# BluePillShematic.net
KiCad netlist of a schematic drawn in Altium Designer
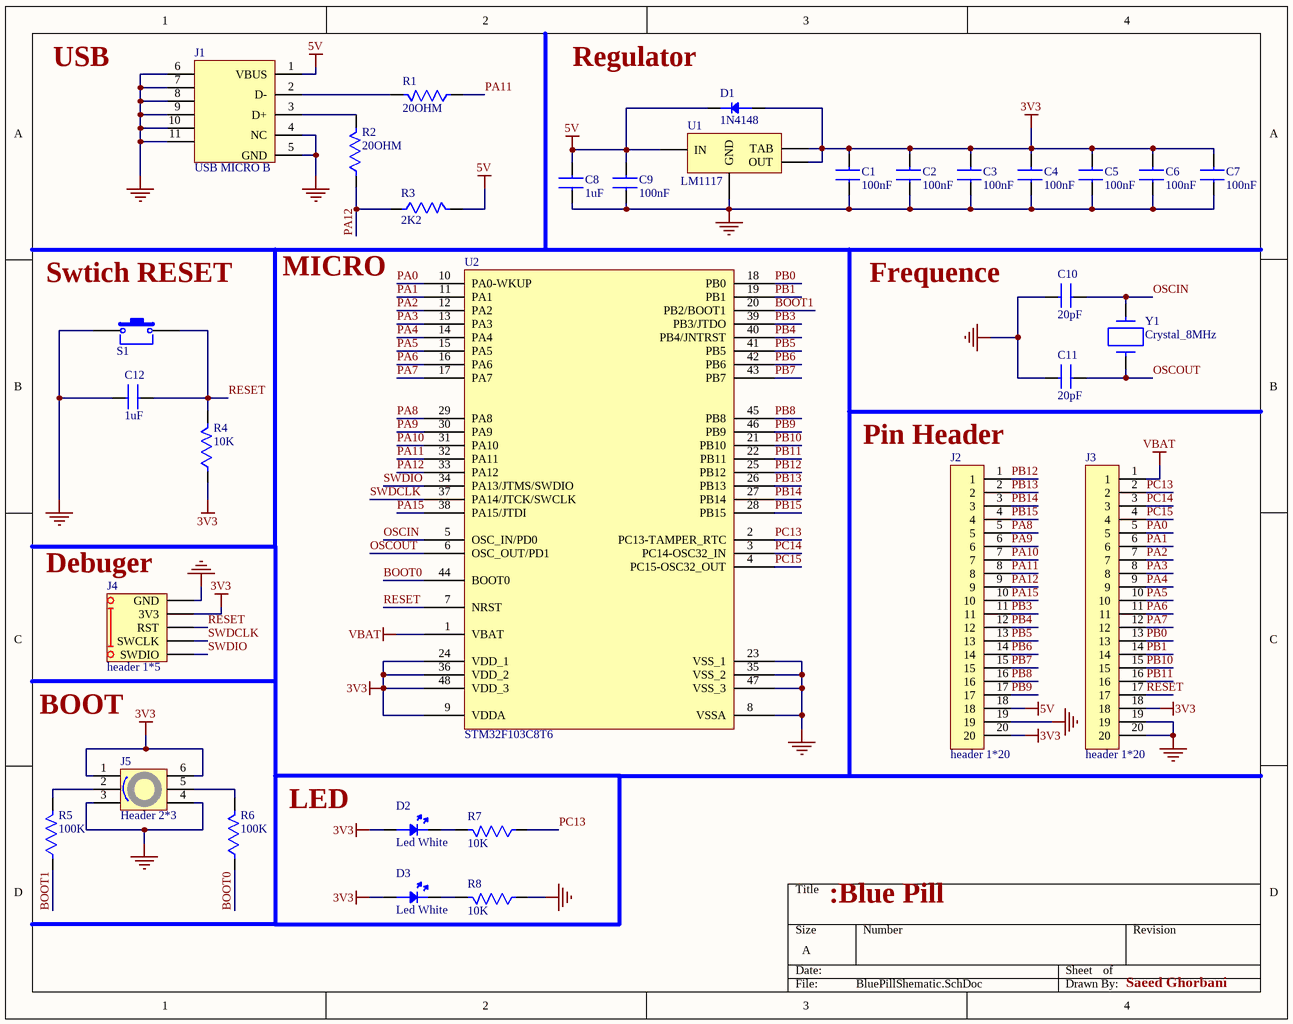
[diagram p0: BluePillShematic.SchDoc]

(export (version "E")
  (design (tool "Eeschema 10.0.6"))
  (components
    (comp (ref "C1")
      (value "100nF")
      (footprint "C0805")
      (description "Cap Ceramic 0.1uF 50V X7R 10% Pad SMD 0805 (1%FR) 125C")
      (fields
        (field (name "MANUFACTURER") "KEMET")
        (field (name "MANUFACTURER PART NUMBER") "M3253504E2A104KZMB")
      )
      (libsource (lib "BluePillShematicLibrary") (part "C0805_100nF"))
    )
    (comp (ref "C2")
      (value "100nF")
      (footprint "C0805")
      (description "Cap Ceramic 0.1uF 50V X7R 10% Pad SMD 0805 (1%FR) 125C")
      (fields
        (field (name "MANUFACTURER") "KEMET")
        (field (name "MANUFACTURER PART NUMBER") "M3253504E2A104KZMB")
      )
      (libsource (lib "BluePillShematicLibrary") (part "C0805_100nF"))
    )
    (comp (ref "C3")
      (value "100nF")
      (footprint "C0805")
      (description "Cap Ceramic 0.1uF 50V X7R 10% Pad SMD 0805 (1%FR) 125C")
      (fields
        (field (name "MANUFACTURER") "KEMET")
        (field (name "MANUFACTURER PART NUMBER") "M3253504E2A104KZMB")
      )
      (libsource (lib "BluePillShematicLibrary") (part "C0805_100nF"))
    )
    (comp (ref "C4")
      (value "100nF")
      (footprint "C0805")
      (description "Cap Ceramic 0.1uF 50V X7R 10% Pad SMD 0805 (1%FR) 125C")
      (fields
        (field (name "MANUFACTURER") "KEMET")
        (field (name "MANUFACTURER PART NUMBER") "M3253504E2A104KZMB")
      )
      (libsource (lib "BluePillShematicLibrary") (part "C0805_100nF"))
    )
    (comp (ref "C5")
      (value "100nF")
      (footprint "C0805")
      (description "Cap Ceramic 0.1uF 50V X7R 10% Pad SMD 0805 (1%FR) 125C")
      (fields
        (field (name "MANUFACTURER") "KEMET")
        (field (name "MANUFACTURER PART NUMBER") "M3253504E2A104KZMB")
      )
      (libsource (lib "BluePillShematicLibrary") (part "C0805_100nF"))
    )
    (comp (ref "C6")
      (value "100nF")
      (footprint "C0805")
      (description "Cap Ceramic 0.1uF 50V X7R 10% Pad SMD 0805 (1%FR) 125C")
      (fields
        (field (name "MANUFACTURER") "KEMET")
        (field (name "MANUFACTURER PART NUMBER") "M3253504E2A104KZMB")
      )
      (libsource (lib "BluePillShematicLibrary") (part "C0805_100nF"))
    )
    (comp (ref "C7")
      (value "100nF")
      (footprint "C0805")
      (description "Cap Ceramic 0.1uF 50V X7R 10% Pad SMD 0805 (1%FR) 125C")
      (fields
        (field (name "MANUFACTURER") "KEMET")
        (field (name "MANUFACTURER PART NUMBER") "M3253504E2A104KZMB")
      )
      (libsource (lib "BluePillShematicLibrary") (part "C0805_100nF"))
    )
    (comp (ref "C8")
      (value "1uF")
      (footprint "C0805")
      (fields
        (field (name "MANUFACTURER") "KEMET")
        (field (name "MANUFACTURER PART NUMBER") "C0805C105K5PACTU")
        (field (name "TOLERANCE") "10%")
      )
      (libsource (lib "BluePillShematicLibrary") (part "C0805_1uF"))
    )
    (comp (ref "C9")
      (value "100nF")
      (footprint "C0805")
      (description "Cap Ceramic 0.1uF 50V X7R 10% Pad SMD 0805 (1%FR) 125C")
      (fields
        (field (name "MANUFACTURER") "KEMET")
        (field (name "MANUFACTURER PART NUMBER") "M3253504E2A104KZMB")
      )
      (libsource (lib "BluePillShematicLibrary") (part "C0805_100nF"))
    )
    (comp (ref "C10")
      (value "20pF")
      (footprint "C0805")
      (description "Cap Ceramic 20pF 50V C0G 10% SMD 0805 125°C Paper T/R")
      (fields
        (field (name "MANUFACTURER") "KEMET")
        (field (name "MANUFACTURER PART NUMBER") "C0805C200K5GAC7800")
      )
      (libsource (lib "BluePillShematicLibrary") (part "C0805_20pF"))
    )
    (comp (ref "C11")
      (value "20pF")
      (footprint "C0805")
      (description "Cap Ceramic 20pF 50V C0G 10% SMD 0805 125°C Paper T/R")
      (fields
        (field (name "MANUFACTURER") "KEMET")
        (field (name "MANUFACTURER PART NUMBER") "C0805C200K5GAC7800")
      )
      (libsource (lib "BluePillShematicLibrary") (part "C0805_20pF"))
    )
    (comp (ref "C12")
      (value "1uF")
      (footprint "C0805")
      (fields
        (field (name "MANUFACTURER") "KEMET")
        (field (name "MANUFACTURER PART NUMBER") "C0805C105K5PACTU")
        (field (name "TOLERANCE") "10%")
      )
      (libsource (lib "BluePillShematicLibrary") (part "C0805_1uF"))
    )
    (comp (ref "D1")
      (value "1N4148")
      (footprint "DO-213-A")
      (description "Diode Switching 75V 0.2A 2-Pin DO-213AA")
      (fields
        (field (name "MANUFACTURER") "Microsemi")
        (field (name "MANUFACTURER PART NUMBER") "1N4148UR-1")
      )
      (libsource (lib "BluePillShematicLibrary") (part "1N4148UR-1"))
    )
    (comp (ref "D2")
      (value "Led White")
      (footprint "LED0603")
      (description "Led White Clear 0603 SMD")
      (fields (field (name "MANUFACTURER") "Inolux") (field (name "MANUFACTURER PART NUMBER") "IN-S63AT5UW"))
      (libsource (lib "BluePillShematicLibrary") (part "LED0603"))
    )
    (comp (ref "D3")
      (value "Led White")
      (footprint "LED0603")
      (description "Led White Clear 0603 SMD")
      (fields (field (name "MANUFACTURER") "Inolux") (field (name "MANUFACTURER PART NUMBER") "IN-S63AT5UW"))
      (libsource (lib "BluePillShematicLibrary") (part "LED0603"))
    )
    (comp (ref "J1")
      (value "USB MICRO B")
      (footprint "USB")
      (description "CONN USB MICRO B RECPT SMT R/A")
      (fields
        (field (name "MANUFACTURER") "Amphenol ICC / FCI")
        (field (name "MANUFACTURER PART NUMBER") "10118194-0001LF")
      )
      (libsource (lib "BluePillShematicLibrary") (part "USB MICRO B"))
    )
    (comp (ref "J2")
      (value "header 1*20")
      (footprint "header 1*20")
      (fields (field (name "MANUFACTURER") "Harwin") (field (name "MANUFACTURER PART NUMBER") "M20-9992045"))
      (libsource (lib "BluePillShematicLibrary") (part "header 1*20"))
    )
    (comp (ref "J3")
      (value "header 1*20")
      (footprint "header 1*20")
      (fields (field (name "MANUFACTURER") "Harwin") (field (name "MANUFACTURER PART NUMBER") "M20-9992045"))
      (libsource (lib "BluePillShematicLibrary") (part "header 1*20"))
    )
    (comp (ref "J4")
      (value "header 1*5")
      (footprint "header 1*5")
      (description "M20 Header,  Pin,  Sil,  Vertical,  5 W")
      (fields (field (name "MANUFACTURER") "Harwin") (field (name "MANUFACTURER PART NUMBER") "M20-9990545"))
      (libsource (lib "BluePillShematicLibrary") (part "header 1*5"))
    )
    (comp (ref "J5")
      (value "Header 2*3")
      (footprint "header 2*3")
      (fields (field (name "MANUFACTURER") "Harwin") (field (name "MANUFACTURER PART NUMBER") "M20-9980345"))
      (libsource (lib "BluePillShematicLibrary") (part "Header 2*3"))
    )
    (comp (ref "R1")
      (value "20OHM")
      (footprint "R0805")
      (description "RES SMD 20 OHM 0.1% 1/8W 0805")
      (fields
        (field (name "MANUFACTURER") "Yageo")
        (field (name "MANUFACTURER PART NUMBER") "RT0805BRD0720RL")
      )
      (libsource (lib "BluePillShematicLibrary") (part "R0805_20OHM"))
    )
    (comp (ref "R2")
      (value "20OHM")
      (footprint "R0805")
      (description "RES SMD 20 OHM 0.1% 1/8W 0805")
      (fields
        (field (name "MANUFACTURER") "Yageo")
        (field (name "MANUFACTURER PART NUMBER") "RT0805BRD0720RL")
      )
      (libsource (lib "BluePillShematicLibrary") (part "R0805_20OHM"))
    )
    (comp (ref "R3")
      (value "2K2")
      (footprint "R0805")
      (description "Res Thick Film 0805 2.2K Ohm 5% 0.125W(1/8W) ±100ppm/C Epoxy Pad SMD T/R")
      (fields
        (field (name "MANUFACTURER") "Yageo")
        (field (name "MANUFACTURER PART NUMBER") "RC0805JR-072K2L")
      )
      (libsource (lib "BluePillShematicLibrary") (part "R0805_2K2"))
    )
    (comp (ref "R4")
      (value "10K")
      (footprint "R0805")
      (description "Res Thick Film 0805 10K Ohm 1% 0.5W(1/2W) ±200ppm/C Pad SMD Automotive T/R")
      (fields
        (field (name "MANUFACTURER") "Yageo")
        (field (name "MANUFACTURER PART NUMBER") "SR0805FR-4710KL")
      )
      (libsource (lib "BluePillShematicLibrary") (part "R0805_10K"))
    )
    (comp (ref "R5")
      (value "100K")
      (footprint "R0805")
      (fields
        (field (name "MANUFACTURER") "Yageo")
        (field (name "MANUFACTURER PART NUMBER") "AC0805FR-7W100KL")
      )
      (libsource (lib "BluePillShematicLibrary") (part "R0805_100K"))
    )
    (comp (ref "R6")
      (value "100K")
      (footprint "R0805")
      (fields
        (field (name "MANUFACTURER") "Yageo")
        (field (name "MANUFACTURER PART NUMBER") "AC0805FR-7W100KL")
      )
      (libsource (lib "BluePillShematicLibrary") (part "R0805_100K"))
    )
    (comp (ref "R7")
      (value "10K")
      (footprint "R0805")
      (description "Res Thick Film 0805 10K Ohm 1% 0.5W(1/2W) ±200ppm/C Pad SMD Automotive T/R")
      (fields
        (field (name "MANUFACTURER") "Yageo")
        (field (name "MANUFACTURER PART NUMBER") "SR0805FR-4710KL")
      )
      (libsource (lib "BluePillShematicLibrary") (part "R0805_10K"))
    )
    (comp (ref "R8")
      (value "10K")
      (footprint "R0805")
      (description "Res Thick Film 0805 10K Ohm 1% 0.5W(1/2W) ±200ppm/C Pad SMD Automotive T/R")
      (fields
        (field (name "MANUFACTURER") "Yageo")
        (field (name "MANUFACTURER PART NUMBER") "SR0805FR-4710KL")
      )
      (libsource (lib "BluePillShematicLibrary") (part "R0805_10K"))
    )
    (comp (ref "S1")
      (value "PTS636SMG25JSMTRLFS")
      (footprint "Switch Reset")
      (fields (field (name "MANUFACTURER") "ITT C&K"))
      (libsource (lib "BluePillShematicLibrary") (part "Switch Reset"))
    )
    (comp (ref "U1")
      (value "LM1117")
      (footprint "LM1117_SOP")
      (fields
        (field (name "MANUFACTURER") "TI National Semiconductor")
        (field (name "MANUFACTURER PART NUMBER") "LM1117MP-3.3/NOPB")
      )
      (libsource (lib "BluePillShematicLibrary") (part "LM1117"))
    )
    (comp (ref "U2")
      (value "STM32F103C8T6")
      (footprint "TQFP48")
      (fields (field (name "MANUFACTURER") "STMicroelectronics"))
      (libsource (lib "BluePillShematicLibrary") (part "STM32F103C8T6"))
    )
    (comp (ref "Y1")
      (value "Crystal_8MHz")
      (footprint "Crystal_8MHz")
      (description "Crystal 8MHz ±30ppm (Tol) ±50ppm (Stability) 18pF FUND 60Ohm 2-Pin HC-49/USX SMD T/R")
      (fields
        (field (name "MANUFACTURER") "ECS International")
        (field (name "MANUFACTURER PART NUMBER") "ECS-80-18-5PX-TR")
      )
      (libsource (lib "BluePillShematicLibrary") (part "Crystal_8MHz"))
    )
  )
  (nets
    (net (code "1") (name "/BOOT0") (class "Default")
      (node (ref "R6") (pin "1") (pinfunction "1_1") (pintype "passive"))
      (node (ref "U2") (pin "44") (pinfunction "BOOT0_44") (pintype "passive"))
    )
    (net (code "2") (name "/BOOT1") (class "Default")
      (node (ref "R5") (pin "1") (pinfunction "1_1") (pintype "passive"))
      (node (ref "U2") (pin "20") (pinfunction "PB2/BOOT1_20") (pintype "passive"))
    )
    (net (code "3") (name "/OSCIN") (class "Default")
      (node (ref "C10") (pin "2") (pinfunction "2_2") (pintype "passive"))
      (node (ref "U2") (pin "5") (pinfunction "OSC_IN/PD0_5") (pintype "passive"))
      (node (ref "Y1") (pin "2") (pinfunction "2_2") (pintype "passive"))
    )
    (net (code "4") (name "/OSCOUT") (class "Default")
      (node (ref "C11") (pin "2") (pinfunction "2_2") (pintype "passive"))
      (node (ref "U2") (pin "6") (pinfunction "OSC_OUT/PD1_6") (pintype "passive"))
      (node (ref "Y1") (pin "1") (pinfunction "1_1") (pintype "passive"))
    )
    (net (code "5") (name "/PA0") (class "Default")
      (node (ref "J3") (pin "5") (pinfunction "5_5") (pintype "passive"))
      (node (ref "U2") (pin "10") (pinfunction "PA0-WKUP_10") (pintype "passive"))
    )
    (net (code "6") (name "/PA1") (class "Default")
      (node (ref "J3") (pin "6") (pinfunction "6_6") (pintype "passive"))
      (node (ref "U2") (pin "11") (pinfunction "PA1_11") (pintype "passive"))
    )
    (net (code "7") (name "/PA2") (class "Default")
      (node (ref "J3") (pin "7") (pinfunction "7_7") (pintype "passive"))
      (node (ref "U2") (pin "12") (pinfunction "PA2_12") (pintype "passive"))
    )
    (net (code "8") (name "/PA3") (class "Default")
      (node (ref "J3") (pin "8") (pinfunction "8_8") (pintype "passive"))
      (node (ref "U2") (pin "13") (pinfunction "PA3_13") (pintype "passive"))
    )
    (net (code "9") (name "/PA4") (class "Default")
      (node (ref "J3") (pin "9") (pinfunction "9_9") (pintype "passive"))
      (node (ref "U2") (pin "14") (pinfunction "PA4_14") (pintype "passive"))
    )
    (net (code "10") (name "/PA5") (class "Default")
      (node (ref "J3") (pin "10") (pinfunction "10_10") (pintype "passive"))
      (node (ref "U2") (pin "15") (pinfunction "PA5_15") (pintype "passive"))
    )
    (net (code "11") (name "/PA6") (class "Default")
      (node (ref "J3") (pin "11") (pinfunction "11_11") (pintype "passive"))
      (node (ref "U2") (pin "16") (pinfunction "PA6_16") (pintype "passive"))
    )
    (net (code "12") (name "/PA7") (class "Default")
      (node (ref "J3") (pin "12") (pinfunction "12_12") (pintype "passive"))
      (node (ref "U2") (pin "17") (pinfunction "PA7_17") (pintype "passive"))
    )
    (net (code "13") (name "/PA8") (class "Default")
      (node (ref "J2") (pin "5") (pinfunction "5_5") (pintype "passive"))
      (node (ref "U2") (pin "29") (pinfunction "PA8_29") (pintype "passive"))
    )
    (net (code "14") (name "/PA9") (class "Default")
      (node (ref "J2") (pin "6") (pinfunction "6_6") (pintype "passive"))
      (node (ref "U2") (pin "30") (pinfunction "PA9_30") (pintype "passive"))
    )
    (net (code "15") (name "/PA10") (class "Default")
      (node (ref "J2") (pin "7") (pinfunction "7_7") (pintype "passive"))
      (node (ref "U2") (pin "31") (pinfunction "PA10_31") (pintype "passive"))
    )
    (net (code "16") (name "/PA11") (class "Default")
      (node (ref "J2") (pin "8") (pinfunction "8_8") (pintype "passive"))
      (node (ref "R1") (pin "1") (pinfunction "1_1") (pintype "passive"))
      (node (ref "U2") (pin "32") (pinfunction "PA11_32") (pintype "passive"))
    )
    (net (code "17") (name "/PA12") (class "Default")
      (node (ref "J2") (pin "9") (pinfunction "9_9") (pintype "passive"))
      (node (ref "R2") (pin "1") (pinfunction "1_1") (pintype "passive"))
      (node (ref "R3") (pin "1") (pinfunction "1_1") (pintype "passive"))
      (node (ref "U2") (pin "33") (pinfunction "PA12_33") (pintype "passive"))
    )
    (net (code "18") (name "/PA15") (class "Default")
      (node (ref "J2") (pin "10") (pinfunction "10_10") (pintype "passive"))
      (node (ref "U2") (pin "38") (pinfunction "PA15/JTDI_38") (pintype "passive"))
    )
    (net (code "19") (name "/PB0") (class "Default")
      (node (ref "J3") (pin "13") (pinfunction "13_13") (pintype "passive"))
      (node (ref "U2") (pin "18") (pinfunction "PB0_18") (pintype "passive"))
    )
    (net (code "20") (name "/PB1") (class "Default")
      (node (ref "J3") (pin "14") (pinfunction "14_14") (pintype "passive"))
      (node (ref "U2") (pin "19") (pinfunction "PB1_19") (pintype "passive"))
    )
    (net (code "21") (name "/PB3") (class "Default")
      (node (ref "J2") (pin "11") (pinfunction "11_11") (pintype "passive"))
      (node (ref "U2") (pin "39") (pinfunction "PB3/JTDO_39") (pintype "passive"))
    )
    (net (code "22") (name "/PB4") (class "Default")
      (node (ref "J2") (pin "12") (pinfunction "12_12") (pintype "passive"))
      (node (ref "U2") (pin "40") (pinfunction "PB4/JNTRST_40") (pintype "passive"))
    )
    (net (code "23") (name "/PB5") (class "Default")
      (node (ref "J2") (pin "13") (pinfunction "13_13") (pintype "passive"))
      (node (ref "U2") (pin "41") (pinfunction "PB5_41") (pintype "passive"))
    )
    (net (code "24") (name "/PB6") (class "Default")
      (node (ref "J2") (pin "14") (pinfunction "14_14") (pintype "passive"))
      (node (ref "U2") (pin "42") (pinfunction "PB6_42") (pintype "passive"))
    )
    (net (code "25") (name "/PB7") (class "Default")
      (node (ref "J2") (pin "15") (pinfunction "15_15") (pintype "passive"))
      (node (ref "U2") (pin "43") (pinfunction "PB7_43") (pintype "passive"))
    )
    (net (code "26") (name "/PB8") (class "Default")
      (node (ref "J2") (pin "16") (pinfunction "16_16") (pintype "passive"))
      (node (ref "U2") (pin "45") (pinfunction "PB8_45") (pintype "passive"))
    )
    (net (code "27") (name "/PB9") (class "Default")
      (node (ref "J2") (pin "17") (pinfunction "17_17") (pintype "passive"))
      (node (ref "U2") (pin "46") (pinfunction "PB9_46") (pintype "passive"))
    )
    (net (code "28") (name "/PB10") (class "Default")
      (node (ref "J3") (pin "15") (pinfunction "15_15") (pintype "passive"))
      (node (ref "U2") (pin "21") (pinfunction "PB10_21") (pintype "passive"))
    )
    (net (code "29") (name "/PB11") (class "Default")
      (node (ref "J3") (pin "16") (pinfunction "16_16") (pintype "passive"))
      (node (ref "U2") (pin "22") (pinfunction "PB11_22") (pintype "passive"))
    )
    (net (code "30") (name "/PB12") (class "Default")
      (node (ref "J2") (pin "1") (pinfunction "1_1") (pintype "passive"))
      (node (ref "U2") (pin "25") (pinfunction "PB12_25") (pintype "passive"))
    )
    (net (code "31") (name "/PB13") (class "Default")
      (node (ref "J2") (pin "2") (pinfunction "2_2") (pintype "passive"))
      (node (ref "U2") (pin "26") (pinfunction "PB13_26") (pintype "passive"))
    )
    (net (code "32") (name "/PB14") (class "Default")
      (node (ref "J2") (pin "3") (pinfunction "3_3") (pintype "passive"))
      (node (ref "U2") (pin "27") (pinfunction "PB14_27") (pintype "passive"))
    )
    (net (code "33") (name "/PB15") (class "Default")
      (node (ref "J2") (pin "4") (pinfunction "4_4") (pintype "passive"))
      (node (ref "U2") (pin "28") (pinfunction "PB15_28") (pintype "passive"))
    )
    (net (code "34") (name "/PC13") (class "Default")
      (node (ref "J3") (pin "2") (pinfunction "2_2") (pintype "passive"))
      (node (ref "R7") (pin "1") (pinfunction "1_1") (pintype "passive"))
      (node (ref "U2") (pin "2") (pinfunction "PC13-TAMPER_RTC_2") (pintype "passive"))
    )
    (net (code "35") (name "/PC14") (class "Default")
      (node (ref "J3") (pin "3") (pinfunction "3_3") (pintype "passive"))
      (node (ref "U2") (pin "3") (pinfunction "PC14-OSC32_IN_3") (pintype "passive"))
    )
    (net (code "36") (name "/PC15") (class "Default")
      (node (ref "J3") (pin "4") (pinfunction "4_4") (pintype "passive"))
      (node (ref "U2") (pin "4") (pinfunction "PC15-OSC32_OUT_4") (pintype "passive"))
    )
    (net (code "37") (name "/RESET") (class "Default")
      (node (ref "C12") (pin "2") (pinfunction "2_2") (pintype "passive"))
      (node (ref "J3") (pin "17") (pinfunction "17_17") (pintype "passive"))
      (node (ref "J4") (pin "3") (pinfunction "RST_3") (pintype "passive"))
      (node (ref "R4") (pin "2") (pinfunction "2_2") (pintype "passive"))
      (node (ref "S1") (pin "2") (pinfunction "2_2") (pintype "passive"))
      (node (ref "U2") (pin "7") (pinfunction "NRST_7") (pintype "passive"))
    )
    (net (code "38") (name "/SWDCLK") (class "Default")
      (node (ref "J4") (pin "4") (pinfunction "SWCLK_4") (pintype "passive"))
      (node (ref "U2") (pin "37") (pinfunction "PA14/JTCK/SWCLK_37") (pintype "passive"))
    )
    (net (code "39") (name "/SWDIO") (class "Default")
      (node (ref "J4") (pin "5") (pinfunction "SWDIO_5") (pintype "passive"))
      (node (ref "U2") (pin "34") (pinfunction "PA13/JTMS/SWDIO_34") (pintype "passive"))
    )
    (net (code "40") (name "3V3") (class "Default")
      (node (ref "C1") (pin "2") (pinfunction "2_2") (pintype "passive"))
      (node (ref "C2") (pin "2") (pinfunction "2_2") (pintype "passive"))
      (node (ref "C3") (pin "2") (pinfunction "2_2") (pintype "passive"))
      (node (ref "C4") (pin "2") (pinfunction "2_2") (pintype "passive"))
      (node (ref "C5") (pin "2") (pinfunction "2_2") (pintype "passive"))
      (node (ref "C6") (pin "2") (pinfunction "2_2") (pintype "passive"))
      (node (ref "C7") (pin "2") (pinfunction "2_2") (pintype "passive"))
      (node (ref "D1") (pin "A") (pinfunction "Anode_A") (pintype "passive"))
      (node (ref "D2") (pin "A") (pinfunction "Anode_A") (pintype "passive"))
      (node (ref "D3") (pin "A") (pinfunction "Anode_A") (pintype "passive"))
      (node (ref "J2") (pin "20") (pinfunction "20_20") (pintype "passive"))
      (node (ref "J3") (pin "18") (pinfunction "18_18") (pintype "passive"))
      (node (ref "J4") (pin "2") (pinfunction "3V3_2") (pintype "passive"))
      (node (ref "J5") (pin "1") (pinfunction "1_1") (pintype "passive"))
      (node (ref "J5") (pin "6") (pinfunction "6_6") (pintype "passive"))
      (node (ref "R4") (pin "1") (pinfunction "1_1") (pintype "passive"))
      (node (ref "U1") (pin "2") (pinfunction "OUT_2") (pintype "passive"))
      (node (ref "U1") (pin "4") (pinfunction "TAB_4") (pintype "passive"))
      (node (ref "U2") (pin "24") (pinfunction "VDD_1_24") (pintype "passive"))
      (node (ref "U2") (pin "36") (pinfunction "VDD_2_36") (pintype "passive"))
      (node (ref "U2") (pin "48") (pinfunction "VDD_3_48") (pintype "passive"))
      (node (ref "U2") (pin "9") (pinfunction "VDDA_9") (pintype "passive"))
    )
    (net (code "41") (name "5V") (class "Default")
      (node (ref "C8") (pin "2") (pinfunction "2_2") (pintype "passive"))
      (node (ref "C9") (pin "2") (pinfunction "2_2") (pintype "passive"))
      (node (ref "D1") (pin "K") (pinfunction "Cathode_K") (pintype "passive"))
      (node (ref "J1") (pin "1") (pinfunction "VBUS_1") (pintype "passive"))
      (node (ref "J2") (pin "18") (pinfunction "18_18") (pintype "passive"))
      (node (ref "R3") (pin "2") (pinfunction "2_2") (pintype "passive"))
      (node (ref "U1") (pin "3") (pinfunction "IN_3") (pintype "passive"))
    )
    (net (code "42") (name "GND") (class "Default")
      (node (ref "C1") (pin "1") (pinfunction "1_1") (pintype "passive"))
      (node (ref "C10") (pin "1") (pinfunction "1_1") (pintype "passive"))
      (node (ref "C11") (pin "1") (pinfunction "1_1") (pintype "passive"))
      (node (ref "C12") (pin "1") (pinfunction "1_1") (pintype "passive"))
      (node (ref "C2") (pin "1") (pinfunction "1_1") (pintype "passive"))
      (node (ref "C3") (pin "1") (pinfunction "1_1") (pintype "passive"))
      (node (ref "C4") (pin "1") (pinfunction "1_1") (pintype "passive"))
      (node (ref "C5") (pin "1") (pinfunction "1_1") (pintype "passive"))
      (node (ref "C6") (pin "1") (pinfunction "1_1") (pintype "passive"))
      (node (ref "C7") (pin "1") (pinfunction "1_1") (pintype "passive"))
      (node (ref "C8") (pin "1") (pinfunction "1_1") (pintype "passive"))
      (node (ref "C9") (pin "1") (pinfunction "1_1") (pintype "passive"))
      (node (ref "J1") (pin "10") (pinfunction "GND_10") (pintype "passive"))
      (node (ref "J1") (pin "11") (pinfunction "GND_11") (pintype "passive"))
      (node (ref "J1") (pin "4") (pinfunction "NC_4") (pintype "passive"))
      (node (ref "J1") (pin "5") (pinfunction "GND_5") (pintype "passive"))
      (node (ref "J1") (pin "6") (pinfunction "GND_6") (pintype "passive"))
      (node (ref "J1") (pin "7") (pinfunction "GND_7") (pintype "passive"))
      (node (ref "J1") (pin "8") (pinfunction "GND_8") (pintype "passive"))
      (node (ref "J1") (pin "9") (pinfunction "GND_9") (pintype "passive"))
      (node (ref "J2") (pin "19") (pinfunction "19_19") (pintype "passive"))
      (node (ref "J3") (pin "19") (pinfunction "19_19") (pintype "passive"))
      (node (ref "J3") (pin "20") (pinfunction "20_20") (pintype "passive"))
      (node (ref "J4") (pin "1") (pinfunction "GND_1") (pintype "passive"))
      (node (ref "J5") (pin "3") (pinfunction "3_3") (pintype "passive"))
      (node (ref "J5") (pin "4") (pinfunction "4_4") (pintype "passive"))
      (node (ref "R8") (pin "1") (pinfunction "1_1") (pintype "passive"))
      (node (ref "S1") (pin "1") (pinfunction "1_1") (pintype "passive"))
      (node (ref "U1") (pin "1") (pinfunction "GND_1") (pintype "passive"))
      (node (ref "U2") (pin "23") (pinfunction "VSS_1_23") (pintype "passive"))
      (node (ref "U2") (pin "35") (pinfunction "VSS_2_35") (pintype "passive"))
      (node (ref "U2") (pin "47") (pinfunction "VSS_3_47") (pintype "passive"))
      (node (ref "U2") (pin "8") (pinfunction "VSSA_8") (pintype "passive"))
    )
    (net (code "43") (name "Net-(D2-Cathode)") (class "Default")
      (node (ref "D2") (pin "K") (pinfunction "Cathode_K") (pintype "passive"))
      (node (ref "R7") (pin "2") (pinfunction "2_2") (pintype "passive"))
    )
    (net (code "44") (name "Net-(D3-Cathode)") (class "Default")
      (node (ref "D3") (pin "K") (pinfunction "Cathode_K") (pintype "passive"))
      (node (ref "R8") (pin "2") (pinfunction "2_2") (pintype "passive"))
    )
    (net (code "45") (name "Net-(J1-D+)") (class "Default")
      (node (ref "J1") (pin "3") (pinfunction "D+_3") (pintype "passive"))
      (node (ref "R2") (pin "2") (pinfunction "2_2") (pintype "passive"))
    )
    (net (code "46") (name "Net-(J1-D-)") (class "Default")
      (node (ref "J1") (pin "2") (pinfunction "D-_2") (pintype "passive"))
      (node (ref "R1") (pin "2") (pinfunction "2_2") (pintype "passive"))
    )
    (net (code "47") (name "Net-(J5-Pad2)") (class "Default")
      (node (ref "J5") (pin "2") (pinfunction "2_2") (pintype "passive"))
      (node (ref "R5") (pin "2") (pinfunction "2_2") (pintype "passive"))
    )
    (net (code "48") (name "Net-(J5-Pad5)") (class "Default")
      (node (ref "J5") (pin "5") (pinfunction "5_5") (pintype "passive"))
      (node (ref "R6") (pin "2") (pinfunction "2_2") (pintype "passive"))
    )
    (net (code "49") (name "VBAT") (class "Default")
      (node (ref "J3") (pin "1") (pinfunction "1_1") (pintype "passive"))
      (node (ref "U2") (pin "1") (pinfunction "VBAT_1") (pintype "passive"))
    )
  )
)
